# Power.net
KiCad netlist of a schematic drawn in Altium Designer
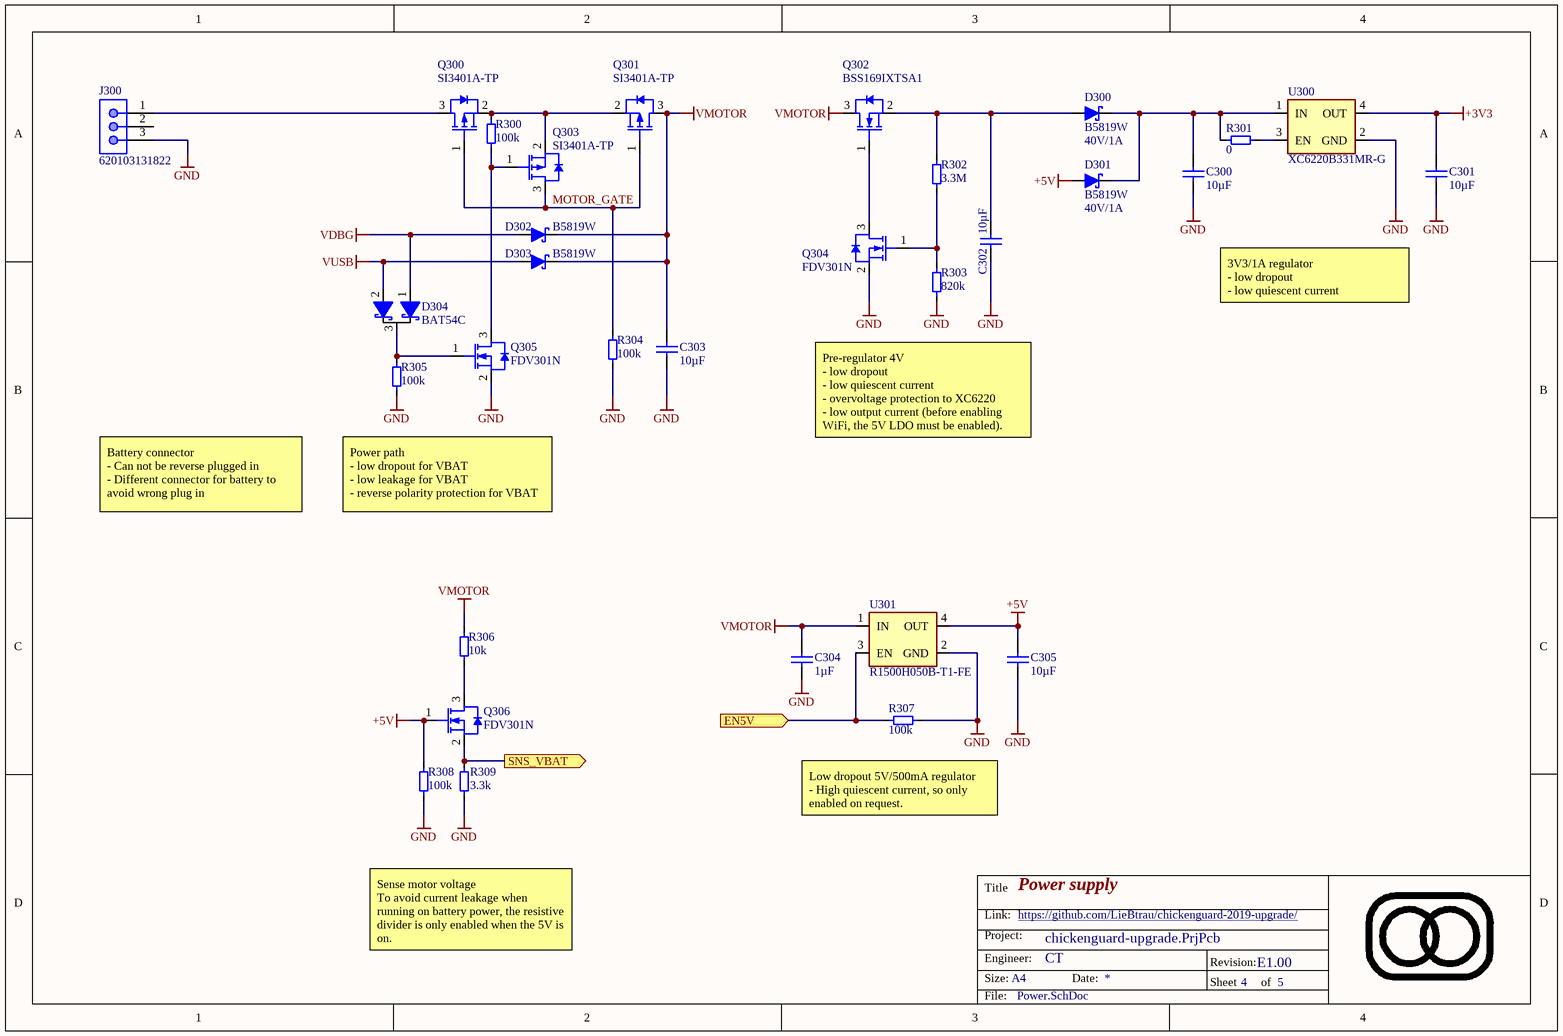
[diagram p0: Power.SchDoc]

(export (version "E")
  (design (tool "Eeschema 10.0.6"))
  (components
    (comp (ref "C300")
      (value "10µF")
      (footprint "1206-C-L")
      (description "WCAP-CSGP Multilayer Ceramic Chip Capacitor, General Purpose, size 1206, X7R, 10µF, 16VDC")
      (fields (field (name "TOLERANCE") "10%") (field (name "JLCPCB PART #") "C13585"))
      (libsource (lib "7c7 Engineering") (part "CAP-NP-2"))
    )
    (comp (ref "C301")
      (value "10µF")
      (footprint "1206-C-L")
      (description "WCAP-CSGP Multilayer Ceramic Chip Capacitor, General Purpose, size 1206, X7R, 10µF, 16VDC")
      (fields (field (name "TOLERANCE") "10%") (field (name "JLCPCB PART #") "C13585"))
      (libsource (lib "7c7 Engineering") (part "CAP-NP-2"))
    )
    (comp (ref "C302")
      (value "10µF")
      (footprint "1206-C-L")
      (description "WCAP-CSGP Multilayer Ceramic Chip Capacitor, General Purpose, size 1206, X7R, 10µF, 16VDC")
      (fields (field (name "TOLERANCE") "10%") (field (name "JLCPCB PART #") "C13585"))
      (libsource (lib "7c7 Engineering") (part "CAP-NP-2"))
    )
    (comp (ref "C303")
      (value "10µF")
      (footprint "1206-C-L")
      (description "WCAP-CSGP Multilayer Ceramic Chip Capacitor, General Purpose, size 1206, X7R, 10µF, 16VDC")
      (fields (field (name "TOLERANCE") "10%") (field (name "JLCPCB PART #") "C13585"))
      (libsource (lib "7c7 Engineering") (part "CAP-NP-2"))
    )
    (comp (ref "C304")
      (value "1µF")
      (footprint "0603-C-N")
      (description "Capacitor MLCC, General Purpose, size 0603, X7R, 1µF, +/-10%, 16V")
      (fields (field (name "TOLERANCE") "10%") (field (name "JLCPCB PART #") "C15849"))
      (libsource (lib "7c7 Engineering") (part "CAP-NP-2"))
    )
    (comp (ref "C305")
      (value "10µF")
      (footprint "1206-C-L")
      (description "WCAP-CSGP Multilayer Ceramic Chip Capacitor, General Purpose, size 1206, X7R, 10µF, 16VDC")
      (fields (field (name "TOLERANCE") "10%") (field (name "JLCPCB PART #") "C13585"))
      (libsource (lib "7c7 Engineering") (part "CAP-NP-2"))
    )
    (comp (ref "D300")
      (value "B5819W")
      (footprint "SOD-123-N")
      (description "Schottky Barrier Rectifier, 40 V, 1 A, -65 to 125 degC, 2-Pin SOD123, RoHS, Tape and Reel")
      (fields
        (field (name "ALTIUM_VALUE") "40V/1A")
        (field (name "MANUFACTURER") "Micro Commercial Components")
        (field (name "JLCPCB PART #") "C8598")
      )
      (libsource (lib "7c7 Engineering") (part "Schottky"))
    )
    (comp (ref "D301")
      (value "B5819W")
      (footprint "SOD-123-N")
      (description "Schottky Barrier Rectifier, 40 V, 1 A, -65 to 125 degC, 2-Pin SOD123, RoHS, Tape and Reel")
      (fields
        (field (name "ALTIUM_VALUE") "40V/1A")
        (field (name "MANUFACTURER") "Micro Commercial Components")
        (field (name "JLCPCB PART #") "C8598")
      )
      (libsource (lib "7c7 Engineering") (part "Schottky"))
    )
    (comp (ref "D302")
      (value "B5819W")
      (footprint "SOD-123-N")
      (description "Schottky Barrier Rectifier, 40 V, 1 A, -65 to 125 degC, 2-Pin SOD123, RoHS, Tape and Reel")
      (fields
        (field (name "MANUFACTURER") "Micro Commercial Components")
        (field (name "JLCPCB PART #") "C8598")
      )
      (libsource (lib "7c7 Engineering") (part "Schottky"))
    )
    (comp (ref "D303")
      (value "B5819W")
      (footprint "SOD-123-N")
      (description "Schottky Barrier Rectifier, 40 V, 1 A, -65 to 125 degC, 2-Pin SOD123, RoHS, Tape and Reel")
      (fields
        (field (name "MANUFACTURER") "Micro Commercial Components")
        (field (name "JLCPCB PART #") "C8598")
      )
      (libsource (lib "7c7 Engineering") (part "Schottky"))
    )
    (comp (ref "D304")
      (value "BAT54C")
      (footprint "SOT-23-3-N")
      (description "Rectifier Diode Small Signal Schottky 30V 0.2A 5ns Automotive 3-Pin SOT-23 T/R")
      (fields (field (name "VOLTAGE") "30V"))
      (libsource (lib "7c7 Engineering") (part "D_SKY_COMMON_CATHODE"))
    )
    (comp (ref "J300")
      (value "620103131822")
      (footprint "620103131822")
      (description "WR-WTB SMT Male Horizontal Shrouded Header, pitch 2mm, 3p")
      (fields (field (name "PUBLISHER") "Wurth Elektronik"))
      (libsource (lib "7c7 Engineering") (part "HDR_3P"))
    )
    (comp (ref "Q300")
      (value "SI3401A-TP")
      (footprint "SOT-23-3-N")
      (description "Trans Mosfet P-ch 30V 4.2A 3-PIN SOT-23 T/r")
      (libsource (lib "7c7 Engineering") (part "PEMOS-GSD-3"))
    )
    (comp (ref "Q301")
      (value "SI3401A-TP")
      (footprint "SOT-23-3-N")
      (description "Trans Mosfet P-ch 30V 4.2A 3-PIN SOT-23 T/r")
      (libsource (lib "7c7 Engineering") (part "PEMOS-GSD-3"))
    )
    (comp (ref "Q302")
      (value "BSS169IXTSA1")
      (footprint "SOT-23-3-N")
      (description "Mosfet, N-Ch, 100V, 0.19A, Sot-23 Rohs Compliant: Yes")
      (fields (field (name "POWER") "360mW"))
      (libsource (lib "7c7 Engineering") (part "NEMOS-GSD-3"))
    )
    (comp (ref "Q303")
      (value "SI3401A-TP")
      (footprint "SOT-23-3-N")
      (description "Trans Mosfet P-ch 30V 4.2A 3-PIN SOT-23 T/r")
      (libsource (lib "7c7 Engineering") (part "PEMOS-GSD-3"))
    )
    (comp (ref "Q304")
      (value "FDV301N")
      (footprint "SOT-23-3-N")
      (description "Transistor MOSFET N-Ch. 25V 220mA 0, 35W 4Ohm SOT23")
      (libsource (lib "7c7 Engineering") (part "NEMOS-GSD-3"))
    )
    (comp (ref "Q305")
      (value "FDV301N")
      (footprint "SOT-23-3-N")
      (description "Transistor MOSFET N-Ch. 25V 220mA 0, 35W 4Ohm SOT23")
      (libsource (lib "7c7 Engineering") (part "NEMOS-GSD-3"))
    )
    (comp (ref "Q306")
      (value "FDV301N")
      (footprint "SOT-23-3-N")
      (description "Transistor MOSFET N-Ch. 25V 220mA 0, 35W 4Ohm SOT23")
      (libsource (lib "7c7 Engineering") (part "NEMOS-GSD-3"))
    )
    (comp (ref "R300")
      (value "100k")
      (footprint "0603-R-N")
      (description "Chip Resistor, Thick Film, General Purpose, 0603, 100mW, 75V, 100 kOhm, +/-1%")
      (fields (field (name "JLCPCB PART #") "C25803") (field (name "TOLERANCE") "1%"))
      (libsource (lib "7c7 Engineering") (part "RES"))
    )
    (comp (ref "R301")
      (value "0")
      (footprint "0603-R-N")
      (description "Chip Jumper, Thick Film, Jumper, 0603, 100mW, 1A, 0 Ohm, <50 mOhm")
      (fields (field (name "TOLERANCE") "50 mOhm") (field (name "JLCPCB PART #") "C21189"))
      (libsource (lib "") (part "RES_2"))
    )
    (comp (ref "R302")
      (value "3.3M")
      (footprint "0603-R-N")
      (description "Res Thick Film 0603 3.3M Ohm 1% 1/10W ±100ppm/°C Molded SMD Paper T/R")
      (fields (field (name "TOLERANCE") "1%") (field (name "Comment") "Resistor 3.3M +/-1% 75V 0603"))
      (libsource (lib "7c7 Engineering") (part "RES"))
    )
    (comp (ref "R303")
      (value "820k")
      (footprint "0603-R-N")
      (description "Res Thick Film 0603 820K Ohm 1% 0.1W(1/10W) ±100ppm/C Pad SMD T/R")
      (fields (field (name "TOLERANCE") "1%") (field (name "Comment") "Resistor 820K +/-1% 75V 0603"))
      (libsource (lib "7c7 Engineering") (part "RES"))
    )
    (comp (ref "R304")
      (value "100k")
      (footprint "0603-R-N")
      (description "Chip Resistor, Thick Film, General Purpose, 0603, 100mW, 75V, 100 kOhm, +/-1%")
      (fields (field (name "JLCPCB PART #") "C25803") (field (name "TOLERANCE") "1%"))
      (libsource (lib "7c7 Engineering") (part "RES"))
    )
    (comp (ref "R305")
      (value "100k")
      (footprint "0603-R-N")
      (description "Chip Resistor, Thick Film, General Purpose, 0603, 100mW, 75V, 100 kOhm, +/-1%")
      (fields (field (name "JLCPCB PART #") "C25803") (field (name "TOLERANCE") "1%"))
      (libsource (lib "7c7 Engineering") (part "RES"))
    )
    (comp (ref "R306")
      (value "10k")
      (footprint "0603-R-N")
      (description "Chip Resistor, Thick Film, General Purpose, 0603, 100mW, 75V, 10 kOhm, +/-1%")
      (fields (field (name "JLCPCB PART #") "C25804") (field (name "TOLERANCE") "1%"))
      (libsource (lib "7c7 Engineering") (part "RES"))
    )
    (comp (ref "R307")
      (value "100k")
      (footprint "0603-R-N")
      (description "Chip Resistor, Thick Film, General Purpose, 0603, 100mW, 75V, 100 kOhm, +/-1%")
      (fields (field (name "JLCPCB PART #") "C25803") (field (name "TOLERANCE") "1%"))
      (libsource (lib "") (part "RES_2"))
    )
    (comp (ref "R308")
      (value "100k")
      (footprint "0603-R-N")
      (description "Chip Resistor, Thick Film, General Purpose, 0603, 100mW, 75V, 100 kOhm, +/-1%")
      (fields (field (name "JLCPCB PART #") "C25803") (field (name "TOLERANCE") "1%"))
      (libsource (lib "") (part "RES_1"))
    )
    (comp (ref "R309")
      (value "3.3k")
      (footprint "0603-R-N")
      (description "Chip Resistor, Thick Film, General Purpose, 0603, 100mW, 75V, 3.3 kOhm, +/-1%")
      (fields (field (name "TOLERANCE") "1%") (field (name "JLCPCB PART #") "C22978"))
      (libsource (lib "") (part "RES_1"))
    )
    (comp (ref "U300")
      (value "XC6220B331MR-G")
      (footprint "SOT25-N")
      (description "Linear Voltage Regulator IC Positive Fixed 1 Output 1A SOT-25-5")
      (libsource (lib "7c7 Engineering") (part "LDO-with-enable"))
    )
    (comp (ref "U301")
      (value "R1500H050B-T1-FE")
      (footprint "SOT-89-MT5_N")
      (description "LDO Regulator Pos 5V 0.5A Automotive 6-Pin(5+Tab) SOT-89 T/R")
      (libsource (lib "7c7 Engineering") (part "LDO-with-enable"))
    )
  )
  (nets
    (net (code "1") (name "+3V3") (class "Default")
      (node (ref "C301") (pin "1") (pinfunction "1_1") (pintype "passive"))
      (node (ref "U300") (pin "4") (pinfunction "OUT_4") (pintype "power_in"))
    )
    (net (code "2") (name "+5V") (class "Default")
      (node (ref "C305") (pin "1") (pinfunction "1_1") (pintype "passive"))
      (node (ref "D301") (pin "2") (pinfunction "A_2") (pintype "passive"))
      (node (ref "Q306") (pin "1") (pinfunction "G_1") (pintype "passive"))
      (node (ref "R308") (pin "1") (pinfunction "1_1") (pintype "passive"))
      (node (ref "U301") (pin "4") (pinfunction "OUT_4") (pintype "power_in"))
    )
    (net (code "3") (name "/EN5V") (class "Default")
      (node (ref "R307") (pin "1") (pinfunction "1_1") (pintype "passive"))
      (node (ref "U301") (pin "3") (pinfunction "EN_3") (pintype "passive"))
    )
    (net (code "4") (name "/MOTOR_GATE") (class "Default")
      (node (ref "Q300") (pin "1") (pinfunction "GATE_1") (pintype "passive"))
      (node (ref "Q301") (pin "1") (pinfunction "GATE_1") (pintype "passive"))
      (node (ref "Q303") (pin "3") (pinfunction "DRAIN_3") (pintype "passive"))
      (node (ref "R304") (pin "2") (pinfunction "2_2") (pintype "passive"))
    )
    (net (code "5") (name "/SNS_VBAT") (class "Default")
      (node (ref "Q306") (pin "2") (pinfunction "S_2") (pintype "passive"))
      (node (ref "R309") (pin "1") (pinfunction "1_1") (pintype "passive"))
    )
    (net (code "6") (name "GND") (class "Default")
      (node (ref "C300") (pin "2") (pinfunction "2_2") (pintype "passive"))
      (node (ref "C301") (pin "2") (pinfunction "2_2") (pintype "passive"))
      (node (ref "C302") (pin "1") (pinfunction "1_1") (pintype "passive"))
      (node (ref "C303") (pin "2") (pinfunction "2_2") (pintype "passive"))
      (node (ref "C304") (pin "2") (pinfunction "2_2") (pintype "passive"))
      (node (ref "C305") (pin "2") (pinfunction "2_2") (pintype "passive"))
      (node (ref "J300") (pin "3") (pinfunction "3_3") (pintype "passive"))
      (node (ref "Q304") (pin "2") (pinfunction "S_2") (pintype "passive"))
      (node (ref "Q305") (pin "2") (pinfunction "S_2") (pintype "passive"))
      (node (ref "R303") (pin "1") (pinfunction "1_1") (pintype "passive"))
      (node (ref "R304") (pin "1") (pinfunction "1_1") (pintype "passive"))
      (node (ref "R305") (pin "1") (pinfunction "1_1") (pintype "passive"))
      (node (ref "R307") (pin "2") (pinfunction "2_2") (pintype "passive"))
      (node (ref "R308") (pin "2") (pinfunction "2_2") (pintype "passive"))
      (node (ref "R309") (pin "2") (pinfunction "2_2") (pintype "passive"))
      (node (ref "U300") (pin "2") (pinfunction "GND_2") (pintype "power_in"))
      (node (ref "U301") (pin "2") (pinfunction "GND_2") (pintype "power_in"))
    )
    (net (code "7") (name "Net-(D300-A)") (class "Default")
      (node (ref "C302") (pin "2") (pinfunction "2_2") (pintype "passive"))
      (node (ref "D300") (pin "2") (pinfunction "A_2") (pintype "passive"))
      (node (ref "Q302") (pin "2") (pinfunction "S_2") (pintype "passive"))
      (node (ref "R302") (pin "2") (pinfunction "2_2") (pintype "passive"))
    )
    (net (code "8") (name "Net-(D300-C)") (class "Default")
      (node (ref "C300") (pin "1") (pinfunction "1_1") (pintype "passive"))
      (node (ref "D300") (pin "1") (pinfunction "C_1") (pintype "passive"))
      (node (ref "D301") (pin "1") (pinfunction "C_1") (pintype "passive"))
      (node (ref "R301") (pin "1") (pinfunction "1_1") (pintype "passive"))
      (node (ref "U300") (pin "1") (pinfunction "IN_1") (pintype "power_in"))
    )
    (net (code "9") (name "Net-(D304-A)") (class "Default")
      (node (ref "D304") (pin "3") (pinfunction "A_3") (pintype "passive"))
      (node (ref "Q305") (pin "1") (pinfunction "G_1") (pintype "passive"))
      (node (ref "R305") (pin "2") (pinfunction "2_2") (pintype "passive"))
    )
    (net (code "10") (name "Net-(Q300-DRAIN)") (class "Default")
      (node (ref "J300") (pin "1") (pinfunction "1_1") (pintype "passive"))
      (node (ref "Q300") (pin "3") (pinfunction "DRAIN_3") (pintype "passive"))
    )
    (net (code "11") (name "Net-(Q300-SOURCE)") (class "Default")
      (node (ref "Q300") (pin "2") (pinfunction "SOURCE_2") (pintype "passive"))
      (node (ref "Q301") (pin "2") (pinfunction "SOURCE_2") (pintype "passive"))
      (node (ref "Q303") (pin "2") (pinfunction "SOURCE_2") (pintype "passive"))
      (node (ref "R300") (pin "2") (pinfunction "2_2") (pintype "passive"))
    )
    (net (code "12") (name "Net-(Q302-G)") (class "Default")
      (node (ref "Q302") (pin "1") (pinfunction "G_1") (pintype "passive"))
      (node (ref "Q304") (pin "3") (pinfunction "D_3") (pintype "passive"))
    )
    (net (code "13") (name "Net-(Q303-GATE)") (class "Default")
      (node (ref "Q303") (pin "1") (pinfunction "GATE_1") (pintype "passive"))
      (node (ref "Q305") (pin "3") (pinfunction "D_3") (pintype "passive"))
      (node (ref "R300") (pin "1") (pinfunction "1_1") (pintype "passive"))
    )
    (net (code "14") (name "Net-(Q304-G)") (class "Default")
      (node (ref "Q304") (pin "1") (pinfunction "G_1") (pintype "passive"))
      (node (ref "R302") (pin "1") (pinfunction "1_1") (pintype "passive"))
      (node (ref "R303") (pin "2") (pinfunction "2_2") (pintype "passive"))
    )
    (net (code "15") (name "Net-(Q306-D)") (class "Default")
      (node (ref "Q306") (pin "3") (pinfunction "D_3") (pintype "passive"))
      (node (ref "R306") (pin "1") (pinfunction "1_1") (pintype "passive"))
    )
    (net (code "16") (name "Net-(U300-EN)") (class "Default")
      (node (ref "R301") (pin "2") (pinfunction "2_2") (pintype "passive"))
      (node (ref "U300") (pin "3") (pinfunction "EN_3") (pintype "passive"))
    )
    (net (code "17") (name "VDBG") (class "Default")
      (node (ref "D302") (pin "2") (pinfunction "A_2") (pintype "passive"))
      (node (ref "D304") (pin "1") (pinfunction "C1_1") (pintype "passive"))
    )
    (net (code "18") (name "VMOTOR") (class "Default")
      (node (ref "C303") (pin "1") (pinfunction "1_1") (pintype "passive"))
      (node (ref "C304") (pin "1") (pinfunction "1_1") (pintype "passive"))
      (node (ref "D302") (pin "1") (pinfunction "C_1") (pintype "passive"))
      (node (ref "D303") (pin "1") (pinfunction "C_1") (pintype "passive"))
      (node (ref "Q301") (pin "3") (pinfunction "DRAIN_3") (pintype "passive"))
      (node (ref "Q302") (pin "3") (pinfunction "D_3") (pintype "passive"))
      (node (ref "R306") (pin "2") (pinfunction "2_2") (pintype "passive"))
      (node (ref "U301") (pin "1") (pinfunction "IN_1") (pintype "power_in"))
    )
    (net (code "19") (name "VUSB") (class "Default")
      (node (ref "D303") (pin "2") (pinfunction "A_2") (pintype "passive"))
      (node (ref "D304") (pin "2") (pinfunction "C2_2") (pintype "passive"))
    )
    (net (code "20") (name "unconnected-(J300-Pad2)") (class "Default")
      (node (ref "J300") (pin "2") (pinfunction "2_2") (pintype "passive"))
    )
  )
)
